# nandboard.net
KiCad netlist of a schematic drawn in EAGLE
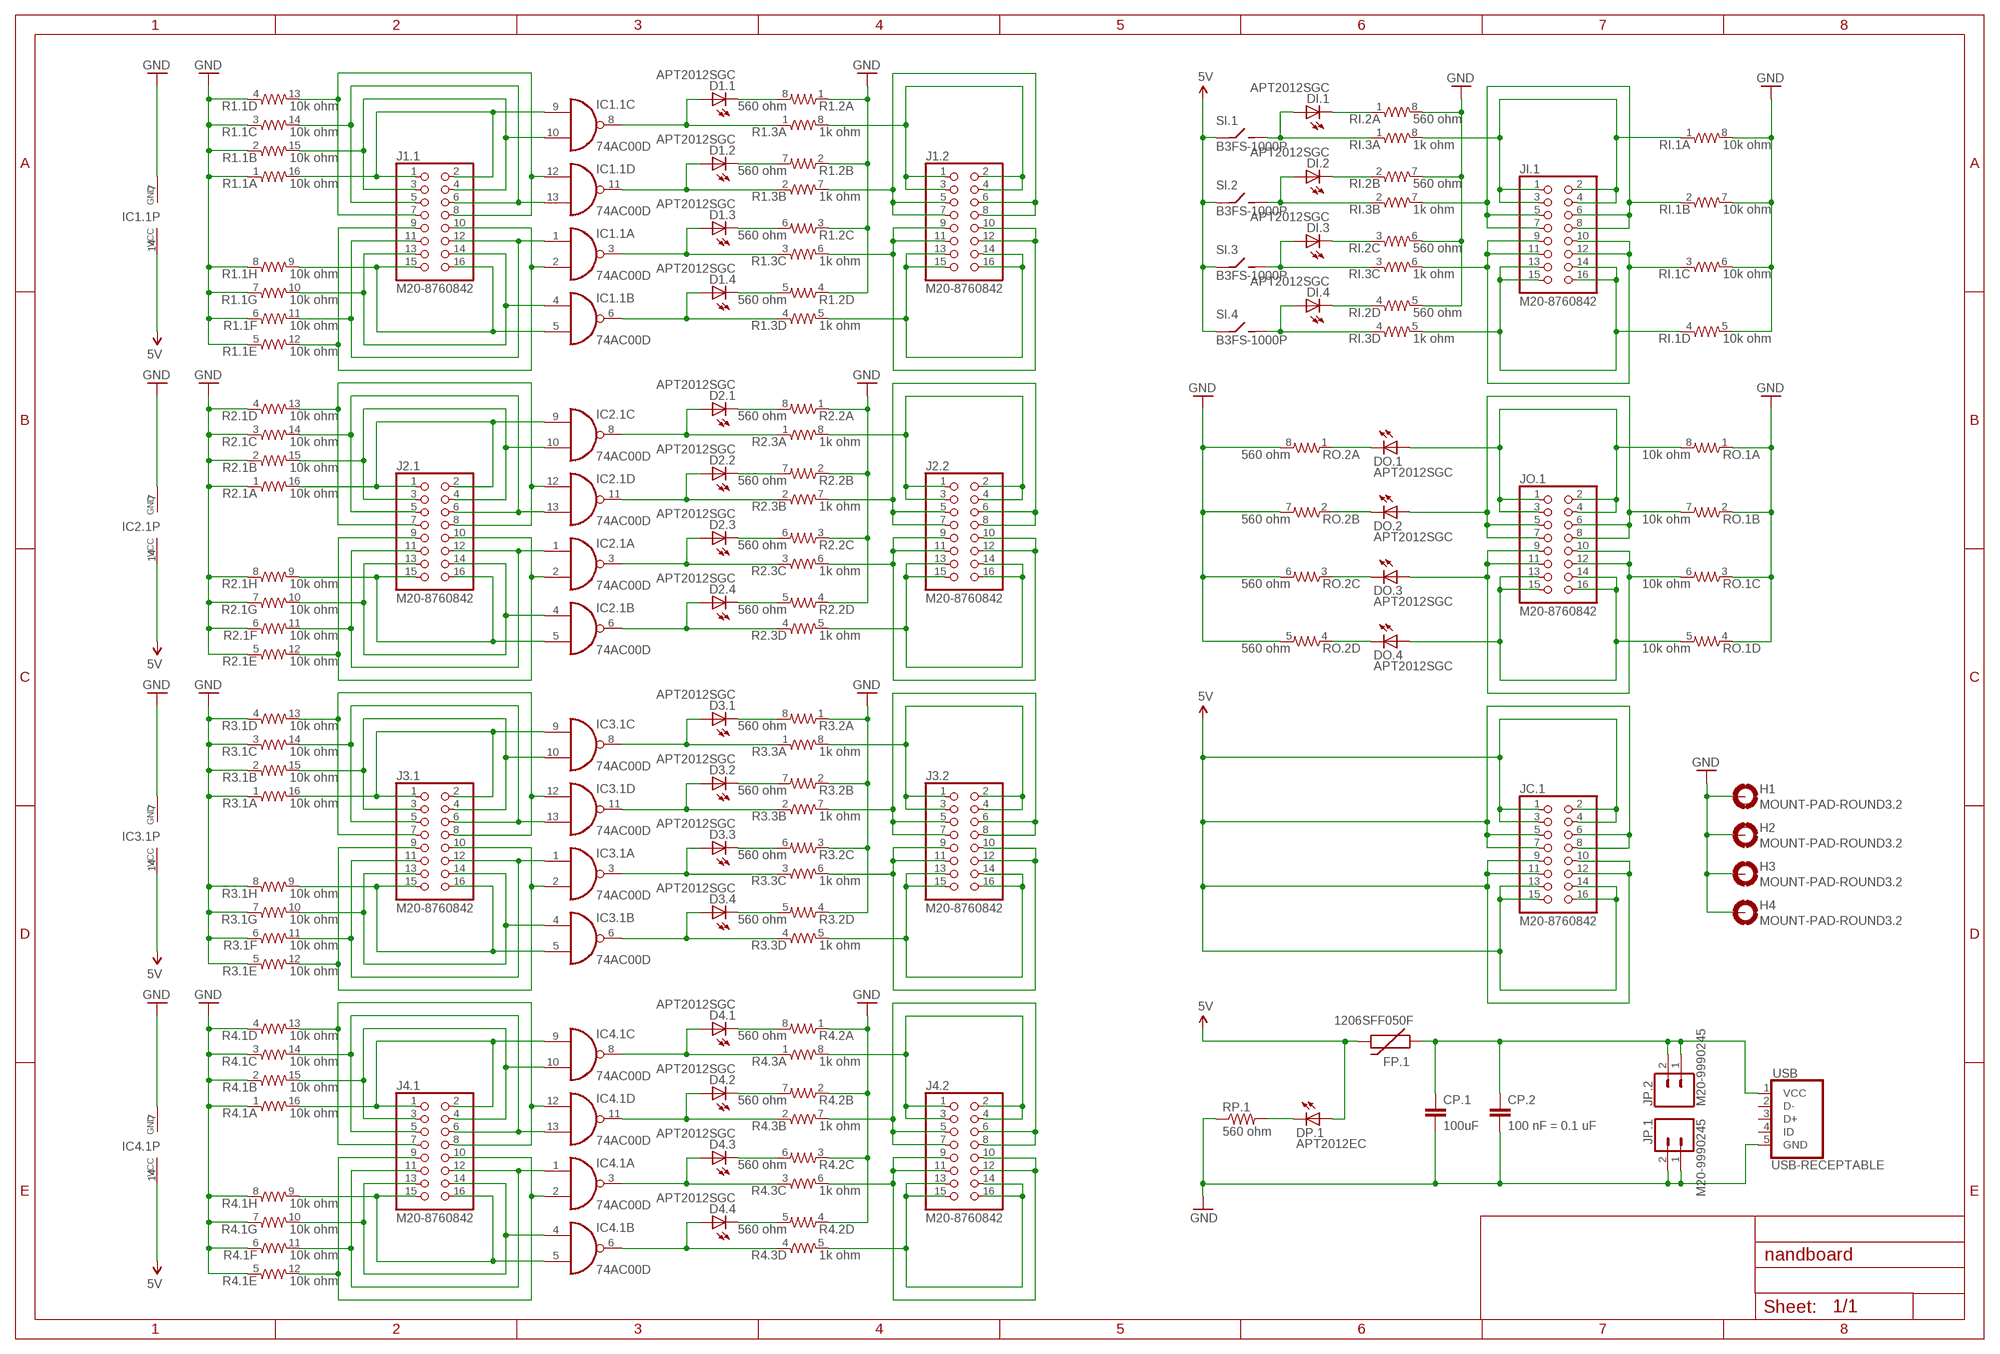
[diagram p0: schematic, sheet 1]

(export (version "E")
  (design (tool "Eeschema 10.0.6"))
  (components
    (comp (ref "CP.1")
      (value "100uF")
      (footprint "eagle-import:C1210")
      (libsource (lib "eagle-import") (part "C-EUC1210"))
    )
    (comp (ref "CP.2")
      (value "100 nF = 0.1 uF")
      (footprint "eagle-import:C0805")
      (libsource (lib "eagle-import") (part "C-EUC0805"))
    )
    (comp (ref "D1.1")
      (value "APT2012SGC")
      (footprint "eagle-import:CHIPLED_0805")
      (libsource (lib "eagle-import") (part "LEDCHIPLED_0805"))
    )
    (comp (ref "D1.2")
      (value "APT2012SGC")
      (footprint "eagle-import:CHIPLED_0805")
      (libsource (lib "eagle-import") (part "LEDCHIPLED_0805"))
    )
    (comp (ref "D1.3")
      (value "APT2012SGC")
      (footprint "eagle-import:CHIPLED_0805")
      (libsource (lib "eagle-import") (part "LEDCHIPLED_0805"))
    )
    (comp (ref "D1.4")
      (value "APT2012SGC")
      (footprint "eagle-import:CHIPLED_0805")
      (libsource (lib "eagle-import") (part "LEDCHIPLED_0805"))
    )
    (comp (ref "D2.1")
      (value "APT2012SGC")
      (footprint "eagle-import:CHIPLED_0805")
      (libsource (lib "eagle-import") (part "LEDCHIPLED_0805"))
    )
    (comp (ref "D2.2")
      (value "APT2012SGC")
      (footprint "eagle-import:CHIPLED_0805")
      (libsource (lib "eagle-import") (part "LEDCHIPLED_0805"))
    )
    (comp (ref "D2.3")
      (value "APT2012SGC")
      (footprint "eagle-import:CHIPLED_0805")
      (libsource (lib "eagle-import") (part "LEDCHIPLED_0805"))
    )
    (comp (ref "D2.4")
      (value "APT2012SGC")
      (footprint "eagle-import:CHIPLED_0805")
      (libsource (lib "eagle-import") (part "LEDCHIPLED_0805"))
    )
    (comp (ref "D3.1")
      (value "APT2012SGC")
      (footprint "eagle-import:CHIPLED_0805")
      (libsource (lib "eagle-import") (part "LEDCHIPLED_0805"))
    )
    (comp (ref "D3.2")
      (value "APT2012SGC")
      (footprint "eagle-import:CHIPLED_0805")
      (libsource (lib "eagle-import") (part "LEDCHIPLED_0805"))
    )
    (comp (ref "D3.3")
      (value "APT2012SGC")
      (footprint "eagle-import:CHIPLED_0805")
      (libsource (lib "eagle-import") (part "LEDCHIPLED_0805"))
    )
    (comp (ref "D3.4")
      (value "APT2012SGC")
      (footprint "eagle-import:CHIPLED_0805")
      (libsource (lib "eagle-import") (part "LEDCHIPLED_0805"))
    )
    (comp (ref "D4.1")
      (value "APT2012SGC")
      (footprint "eagle-import:CHIPLED_0805")
      (libsource (lib "eagle-import") (part "LEDCHIPLED_0805"))
    )
    (comp (ref "D4.2")
      (value "APT2012SGC")
      (footprint "eagle-import:CHIPLED_0805")
      (libsource (lib "eagle-import") (part "LEDCHIPLED_0805"))
    )
    (comp (ref "D4.3")
      (value "APT2012SGC")
      (footprint "eagle-import:CHIPLED_0805")
      (libsource (lib "eagle-import") (part "LEDCHIPLED_0805"))
    )
    (comp (ref "D4.4")
      (value "APT2012SGC")
      (footprint "eagle-import:CHIPLED_0805")
      (libsource (lib "eagle-import") (part "LEDCHIPLED_0805"))
    )
    (comp (ref "DI.1")
      (value "APT2012SGC")
      (footprint "eagle-import:CHIPLED_0805")
      (libsource (lib "eagle-import") (part "LEDCHIPLED_0805"))
    )
    (comp (ref "DI.2")
      (value "APT2012SGC")
      (footprint "eagle-import:CHIPLED_0805")
      (libsource (lib "eagle-import") (part "LEDCHIPLED_0805"))
    )
    (comp (ref "DI.3")
      (value "APT2012SGC")
      (footprint "eagle-import:CHIPLED_0805")
      (libsource (lib "eagle-import") (part "LEDCHIPLED_0805"))
    )
    (comp (ref "DI.4")
      (value "APT2012SGC")
      (footprint "eagle-import:CHIPLED_0805")
      (libsource (lib "eagle-import") (part "LEDCHIPLED_0805"))
    )
    (comp (ref "DO.1")
      (value "APT2012SGC")
      (footprint "eagle-import:CHIPLED_0805")
      (libsource (lib "eagle-import") (part "LEDCHIPLED_0805"))
    )
    (comp (ref "DO.2")
      (value "APT2012SGC")
      (footprint "eagle-import:CHIPLED_0805")
      (libsource (lib "eagle-import") (part "LEDCHIPLED_0805"))
    )
    (comp (ref "DO.3")
      (value "APT2012SGC")
      (footprint "eagle-import:CHIPLED_0805")
      (libsource (lib "eagle-import") (part "LEDCHIPLED_0805"))
    )
    (comp (ref "DO.4")
      (value "APT2012SGC")
      (footprint "eagle-import:CHIPLED_0805")
      (libsource (lib "eagle-import") (part "LEDCHIPLED_0805"))
    )
    (comp (ref "DP.1")
      (value "APT2012EC")
      (footprint "eagle-import:CHIPLED_0805")
      (libsource (lib "eagle-import") (part "LEDCHIPLED_0805"))
    )
    (comp (ref "FP.1")
      (value "1206SFF050F")
      (footprint "eagle-import:PTC-1206")
      (libsource (lib "eagle-import") (part "PTCSMD"))
    )
    (comp (ref "H1")
      (value "MOUNT-PAD-ROUND3.2")
      (footprint "eagle-import:3,2-PAD")
      (libsource (lib "eagle-import") (part "MOUNT-PAD-ROUND3.2"))
    )
    (comp (ref "H2")
      (value "MOUNT-PAD-ROUND3.2")
      (footprint "eagle-import:3,2-PAD")
      (libsource (lib "eagle-import") (part "MOUNT-PAD-ROUND3.2"))
    )
    (comp (ref "H3")
      (value "MOUNT-PAD-ROUND3.2")
      (footprint "eagle-import:3,2-PAD")
      (libsource (lib "eagle-import") (part "MOUNT-PAD-ROUND3.2"))
    )
    (comp (ref "H4")
      (value "MOUNT-PAD-ROUND3.2")
      (footprint "eagle-import:3,2-PAD")
      (libsource (lib "eagle-import") (part "MOUNT-PAD-ROUND3.2"))
    )
    (comp (ref "IC1.1")
      (value "74AC00D")
      (footprint "eagle-import:SO14")
      (libsource (lib "eagle-import") (part "7400DAC"))
    )
    (comp (ref "IC2.1")
      (value "74AC00D")
      (footprint "eagle-import:SO14")
      (libsource (lib "eagle-import") (part "7400DAC"))
    )
    (comp (ref "IC3.1")
      (value "74AC00D")
      (footprint "eagle-import:SO14")
      (libsource (lib "eagle-import") (part "7400DAC"))
    )
    (comp (ref "IC4.1")
      (value "74AC00D")
      (footprint "eagle-import:SO14")
      (libsource (lib "eagle-import") (part "7400DAC"))
    )
    (comp (ref "J1.1")
      (value "M20-8760842")
      (footprint "eagle-import:2X08_SMT")
      (libsource (lib "eagle-import") (part "PINHD-2X8SMT"))
    )
    (comp (ref "J1.2")
      (value "M20-8760842")
      (footprint "eagle-import:2X08_SMT")
      (libsource (lib "eagle-import") (part "PINHD-2X8SMT"))
    )
    (comp (ref "J2.1")
      (value "M20-8760842")
      (footprint "eagle-import:2X08_SMT")
      (libsource (lib "eagle-import") (part "PINHD-2X8SMT"))
    )
    (comp (ref "J2.2")
      (value "M20-8760842")
      (footprint "eagle-import:2X08_SMT")
      (libsource (lib "eagle-import") (part "PINHD-2X8SMT"))
    )
    (comp (ref "J3.1")
      (value "M20-8760842")
      (footprint "eagle-import:2X08_SMT")
      (libsource (lib "eagle-import") (part "PINHD-2X8SMT"))
    )
    (comp (ref "J3.2")
      (value "M20-8760842")
      (footprint "eagle-import:2X08_SMT")
      (libsource (lib "eagle-import") (part "PINHD-2X8SMT"))
    )
    (comp (ref "J4.1")
      (value "M20-8760842")
      (footprint "eagle-import:2X08_SMT")
      (libsource (lib "eagle-import") (part "PINHD-2X8SMT"))
    )
    (comp (ref "J4.2")
      (value "M20-8760842")
      (footprint "eagle-import:2X08_SMT")
      (libsource (lib "eagle-import") (part "PINHD-2X8SMT"))
    )
    (comp (ref "JC.1")
      (value "M20-8760842")
      (footprint "eagle-import:2X08_SMT")
      (libsource (lib "eagle-import") (part "PINHD-2X8SMT"))
    )
    (comp (ref "JI.1")
      (value "M20-8760842")
      (footprint "eagle-import:2X08_SMT")
      (libsource (lib "eagle-import") (part "PINHD-2X8SMT"))
    )
    (comp (ref "JO.1")
      (value "M20-8760842")
      (footprint "eagle-import:2X08_SMT")
      (libsource (lib "eagle-import") (part "PINHD-2X8SMT"))
    )
    (comp (ref "JP.1")
      (value "M20-9990245")
      (footprint "eagle-import:1X02")
      (libsource (lib "eagle-import") (part "CONN_02"))
    )
    (comp (ref "JP.2")
      (value "M20-9990245")
      (footprint "eagle-import:1X02")
      (libsource (lib "eagle-import") (part "CONN_02"))
    )
    (comp (ref "R1.1")
      (value "10k ohm")
      (footprint "eagle-import:742-16")
      (libsource (lib "eagle-import") (part "742-16_S"))
    )
    (comp (ref "R1.2")
      (value "560 ohm")
      (footprint "eagle-import:742-8")
      (libsource (lib "eagle-import") (part "742-8_S"))
    )
    (comp (ref "R1.3")
      (value "1k ohm")
      (footprint "eagle-import:742-8")
      (libsource (lib "eagle-import") (part "742-8_S"))
    )
    (comp (ref "R2.1")
      (value "10k ohm")
      (footprint "eagle-import:742-16")
      (libsource (lib "eagle-import") (part "742-16_S"))
    )
    (comp (ref "R2.2")
      (value "560 ohm")
      (footprint "eagle-import:742-8")
      (libsource (lib "eagle-import") (part "742-8_S"))
    )
    (comp (ref "R2.3")
      (value "1k ohm")
      (footprint "eagle-import:742-8")
      (libsource (lib "eagle-import") (part "742-8_S"))
    )
    (comp (ref "R3.1")
      (value "10k ohm")
      (footprint "eagle-import:742-16")
      (libsource (lib "eagle-import") (part "742-16_S"))
    )
    (comp (ref "R3.2")
      (value "560 ohm")
      (footprint "eagle-import:742-8")
      (libsource (lib "eagle-import") (part "742-8_S"))
    )
    (comp (ref "R3.3")
      (value "1k ohm")
      (footprint "eagle-import:742-8")
      (libsource (lib "eagle-import") (part "742-8_S"))
    )
    (comp (ref "R4.1")
      (value "10k ohm")
      (footprint "eagle-import:742-16")
      (libsource (lib "eagle-import") (part "742-16_S"))
    )
    (comp (ref "R4.2")
      (value "560 ohm")
      (footprint "eagle-import:742-8")
      (libsource (lib "eagle-import") (part "742-8_S"))
    )
    (comp (ref "R4.3")
      (value "1k ohm")
      (footprint "eagle-import:742-8")
      (libsource (lib "eagle-import") (part "742-8_S"))
    )
    (comp (ref "RI.1")
      (value "10k ohm")
      (footprint "eagle-import:742-8")
      (libsource (lib "eagle-import") (part "742-8_S"))
    )
    (comp (ref "RI.2")
      (value "560 ohm")
      (footprint "eagle-import:742-8")
      (libsource (lib "eagle-import") (part "742-8_S"))
    )
    (comp (ref "RI.3")
      (value "1k ohm")
      (footprint "eagle-import:742-8")
      (libsource (lib "eagle-import") (part "742-8_S"))
    )
    (comp (ref "RO.1")
      (value "10k ohm")
      (footprint "eagle-import:742-8")
      (libsource (lib "eagle-import") (part "742-8_S"))
    )
    (comp (ref "RO.2")
      (value "560 ohm")
      (footprint "eagle-import:742-8")
      (libsource (lib "eagle-import") (part "742-8_S"))
    )
    (comp (ref "RP.1")
      (value "560 ohm")
      (footprint "eagle-import:R0603")
      (libsource (lib "eagle-import") (part "R-US_R0603"))
    )
    (comp (ref "SI.1")
      (value "B3FS-1000P")
      (footprint "eagle-import:B3FS-1000")
      (libsource (lib "eagle-import") (part "SPSTB3FS-1000"))
    )
    (comp (ref "SI.2")
      (value "B3FS-1000P")
      (footprint "eagle-import:B3FS-1000")
      (libsource (lib "eagle-import") (part "SPSTB3FS-1000"))
    )
    (comp (ref "SI.3")
      (value "B3FS-1000P")
      (footprint "eagle-import:B3FS-1000")
      (libsource (lib "eagle-import") (part "SPSTB3FS-1000"))
    )
    (comp (ref "SI.4")
      (value "B3FS-1000P")
      (footprint "eagle-import:B3FS-1000")
      (libsource (lib "eagle-import") (part "SPSTB3FS-1000"))
    )
    (comp (ref "USB")
      (value "USB-RECEPTABLE")
      (footprint "eagle-import:FCI-10103594-0001LF")
      (libsource (lib "eagle-import") (part "USB-RECEPTABLE"))
    )
  )
  (nets
    (net (code "1") (name "5V") (class "Default")
      (node (ref "DP.1") (pin "A") (pinfunction "A_A") (pintype "passive"))
      (node (ref "FP.1") (pin "2") (pinfunction "2_2") (pintype "bidirectional"))
      (node (ref "IC1.1") (pin "14") (pinfunction "VCC_14") (pintype "power_in"))
      (node (ref "IC2.1") (pin "14") (pinfunction "VCC_14") (pintype "power_in"))
      (node (ref "IC3.1") (pin "14") (pinfunction "VCC_14") (pintype "power_in"))
      (node (ref "IC4.1") (pin "14") (pinfunction "VCC_14") (pintype "power_in"))
      (node (ref "JC.1") (pin "1") (pinfunction "1_1") (pintype "passive"))
      (node (ref "JC.1") (pin "10") (pinfunction "10_10") (pintype "passive"))
      (node (ref "JC.1") (pin "11") (pinfunction "11_11") (pintype "passive"))
      (node (ref "JC.1") (pin "12") (pinfunction "12_12") (pintype "passive"))
      (node (ref "JC.1") (pin "13") (pinfunction "13_13") (pintype "passive"))
      (node (ref "JC.1") (pin "14") (pinfunction "14_14") (pintype "passive"))
      (node (ref "JC.1") (pin "15") (pinfunction "15_15") (pintype "passive"))
      (node (ref "JC.1") (pin "16") (pinfunction "16_16") (pintype "passive"))
      (node (ref "JC.1") (pin "2") (pinfunction "2_2") (pintype "passive"))
      (node (ref "JC.1") (pin "3") (pinfunction "3_3") (pintype "passive"))
      (node (ref "JC.1") (pin "4") (pinfunction "4_4") (pintype "passive"))
      (node (ref "JC.1") (pin "5") (pinfunction "5_5") (pintype "passive"))
      (node (ref "JC.1") (pin "6") (pinfunction "6_6") (pintype "passive"))
      (node (ref "JC.1") (pin "7") (pinfunction "7_7") (pintype "passive"))
      (node (ref "JC.1") (pin "8") (pinfunction "8_8") (pintype "passive"))
      (node (ref "JC.1") (pin "9") (pinfunction "9_9") (pintype "passive"))
      (node (ref "SI.1") (pin "1") (pinfunction "A_1") (pintype "bidirectional"))
      (node (ref "SI.1") (pin "2") (pinfunction "A_2") (pintype "bidirectional"))
      (node (ref "SI.2") (pin "1") (pinfunction "A_1") (pintype "bidirectional"))
      (node (ref "SI.2") (pin "2") (pinfunction "A_2") (pintype "bidirectional"))
      (node (ref "SI.3") (pin "1") (pinfunction "A_1") (pintype "bidirectional"))
      (node (ref "SI.3") (pin "2") (pinfunction "A_2") (pintype "bidirectional"))
      (node (ref "SI.4") (pin "1") (pinfunction "A_1") (pintype "bidirectional"))
      (node (ref "SI.4") (pin "2") (pinfunction "A_2") (pintype "bidirectional"))
    )
    (net (code "2") (name "GND") (class "Default")
      (node (ref "CP.1") (pin "2") (pinfunction "2_2") (pintype "passive"))
      (node (ref "CP.2") (pin "2") (pinfunction "2_2") (pintype "passive"))
      (node (ref "H1") (pin "B3,2") (pinfunction "MOUNT_B3,2") (pintype "passive"))
      (node (ref "H2") (pin "B3,2") (pinfunction "MOUNT_B3,2") (pintype "passive"))
      (node (ref "H3") (pin "B3,2") (pinfunction "MOUNT_B3,2") (pintype "passive"))
      (node (ref "H4") (pin "B3,2") (pinfunction "MOUNT_B3,2") (pintype "passive"))
      (node (ref "IC1.1") (pin "7") (pinfunction "GND_7") (pintype "power_in"))
      (node (ref "IC2.1") (pin "7") (pinfunction "GND_7") (pintype "power_in"))
      (node (ref "IC3.1") (pin "7") (pinfunction "GND_7") (pintype "power_in"))
      (node (ref "IC4.1") (pin "7") (pinfunction "GND_7") (pintype "power_in"))
      (node (ref "JP.1") (pin "1") (pinfunction "1_1") (pintype "passive"))
      (node (ref "JP.1") (pin "2") (pinfunction "2_2") (pintype "passive"))
      (node (ref "R1.1") (pin "1") (pinfunction "1_1") (pintype "passive"))
      (node (ref "R1.1") (pin "2") (pinfunction "1_2") (pintype "passive"))
      (node (ref "R1.1") (pin "3") (pinfunction "1_3") (pintype "passive"))
      (node (ref "R1.1") (pin "4") (pinfunction "1_4") (pintype "passive"))
      (node (ref "R1.1") (pin "5") (pinfunction "1_5") (pintype "passive"))
      (node (ref "R1.1") (pin "6") (pinfunction "1_6") (pintype "passive"))
      (node (ref "R1.1") (pin "7") (pinfunction "1_7") (pintype "passive"))
      (node (ref "R1.1") (pin "8") (pinfunction "1_8") (pintype "passive"))
      (node (ref "R1.2") (pin "1") (pinfunction "1_1") (pintype "passive"))
      (node (ref "R1.2") (pin "2") (pinfunction "1_2") (pintype "passive"))
      (node (ref "R1.2") (pin "3") (pinfunction "1_3") (pintype "passive"))
      (node (ref "R1.2") (pin "4") (pinfunction "1_4") (pintype "passive"))
      (node (ref "R2.1") (pin "1") (pinfunction "1_1") (pintype "passive"))
      (node (ref "R2.1") (pin "2") (pinfunction "1_2") (pintype "passive"))
      (node (ref "R2.1") (pin "3") (pinfunction "1_3") (pintype "passive"))
      (node (ref "R2.1") (pin "4") (pinfunction "1_4") (pintype "passive"))
      (node (ref "R2.1") (pin "5") (pinfunction "1_5") (pintype "passive"))
      (node (ref "R2.1") (pin "6") (pinfunction "1_6") (pintype "passive"))
      (node (ref "R2.1") (pin "7") (pinfunction "1_7") (pintype "passive"))
      (node (ref "R2.1") (pin "8") (pinfunction "1_8") (pintype "passive"))
      (node (ref "R2.2") (pin "1") (pinfunction "1_1") (pintype "passive"))
      (node (ref "R2.2") (pin "2") (pinfunction "1_2") (pintype "passive"))
      (node (ref "R2.2") (pin "3") (pinfunction "1_3") (pintype "passive"))
      (node (ref "R2.2") (pin "4") (pinfunction "1_4") (pintype "passive"))
      (node (ref "R3.1") (pin "1") (pinfunction "1_1") (pintype "passive"))
      (node (ref "R3.1") (pin "2") (pinfunction "1_2") (pintype "passive"))
      (node (ref "R3.1") (pin "3") (pinfunction "1_3") (pintype "passive"))
      (node (ref "R3.1") (pin "4") (pinfunction "1_4") (pintype "passive"))
      (node (ref "R3.1") (pin "5") (pinfunction "1_5") (pintype "passive"))
      (node (ref "R3.1") (pin "6") (pinfunction "1_6") (pintype "passive"))
      (node (ref "R3.1") (pin "7") (pinfunction "1_7") (pintype "passive"))
      (node (ref "R3.1") (pin "8") (pinfunction "1_8") (pintype "passive"))
      (node (ref "R3.2") (pin "1") (pinfunction "1_1") (pintype "passive"))
      (node (ref "R3.2") (pin "2") (pinfunction "1_2") (pintype "passive"))
      (node (ref "R3.2") (pin "3") (pinfunction "1_3") (pintype "passive"))
      (node (ref "R3.2") (pin "4") (pinfunction "1_4") (pintype "passive"))
      (node (ref "R4.1") (pin "1") (pinfunction "1_1") (pintype "passive"))
      (node (ref "R4.1") (pin "2") (pinfunction "1_2") (pintype "passive"))
      (node (ref "R4.1") (pin "3") (pinfunction "1_3") (pintype "passive"))
      (node (ref "R4.1") (pin "4") (pinfunction "1_4") (pintype "passive"))
      (node (ref "R4.1") (pin "5") (pinfunction "1_5") (pintype "passive"))
      (node (ref "R4.1") (pin "6") (pinfunction "1_6") (pintype "passive"))
      (node (ref "R4.1") (pin "7") (pinfunction "1_7") (pintype "passive"))
      (node (ref "R4.1") (pin "8") (pinfunction "1_8") (pintype "passive"))
      (node (ref "R4.2") (pin "1") (pinfunction "1_1") (pintype "passive"))
      (node (ref "R4.2") (pin "2") (pinfunction "1_2") (pintype "passive"))
      (node (ref "R4.2") (pin "3") (pinfunction "1_3") (pintype "passive"))
      (node (ref "R4.2") (pin "4") (pinfunction "1_4") (pintype "passive"))
      (node (ref "RI.1") (pin "5") (pinfunction "2_5") (pintype "passive"))
      (node (ref "RI.1") (pin "6") (pinfunction "2_6") (pintype "passive"))
      (node (ref "RI.1") (pin "7") (pinfunction "2_7") (pintype "passive"))
      (node (ref "RI.1") (pin "8") (pinfunction "2_8") (pintype "passive"))
      (node (ref "RI.2") (pin "5") (pinfunction "2_5") (pintype "passive"))
      (node (ref "RI.2") (pin "6") (pinfunction "2_6") (pintype "passive"))
      (node (ref "RI.2") (pin "7") (pinfunction "2_7") (pintype "passive"))
      (node (ref "RI.2") (pin "8") (pinfunction "2_8") (pintype "passive"))
      (node (ref "RO.1") (pin "1") (pinfunction "1_1") (pintype "passive"))
      (node (ref "RO.1") (pin "2") (pinfunction "1_2") (pintype "passive"))
      (node (ref "RO.1") (pin "3") (pinfunction "1_3") (pintype "passive"))
      (node (ref "RO.1") (pin "4") (pinfunction "1_4") (pintype "passive"))
      (node (ref "RO.2") (pin "5") (pinfunction "2_5") (pintype "passive"))
      (node (ref "RO.2") (pin "6") (pinfunction "2_6") (pintype "passive"))
      (node (ref "RO.2") (pin "7") (pinfunction "2_7") (pintype "passive"))
      (node (ref "RO.2") (pin "8") (pinfunction "2_8") (pintype "passive"))
      (node (ref "RP.1") (pin "1") (pinfunction "1_1") (pintype "passive"))
      (node (ref "USB") (pin "5") (pinfunction "GND_5") (pintype "bidirectional"))
    )
    (net (code "3") (name "Net-(DI.1-PadA)") (class "Default")
      (node (ref "DI.1") (pin "A") (pinfunction "A_A") (pintype "passive"))
      (node (ref "RI.3") (pin "1") (pinfunction "1_1") (pintype "passive"))
      (node (ref "SI.1") (pin "3") (pinfunction "B_3") (pintype "bidirectional"))
      (node (ref "SI.1") (pin "4") (pinfunction "B_4") (pintype "bidirectional"))
    )
    (net (code "4") (name "Net-(DI.1-PadC)") (class "Default")
      (node (ref "DI.1") (pin "C") (pinfunction "C_C") (pintype "passive"))
      (node (ref "RI.2") (pin "1") (pinfunction "1_1") (pintype "passive"))
    )
    (net (code "5") (name "Net-(DO.1-PadC)") (class "Default")
      (node (ref "DO.1") (pin "C") (pinfunction "C_C") (pintype "passive"))
      (node (ref "RO.2") (pin "1") (pinfunction "1_1") (pintype "passive"))
    )
    (net (code "6") (name "Net-(DP.1-PadC)") (class "Default")
      (node (ref "DP.1") (pin "C") (pinfunction "C_C") (pintype "passive"))
      (node (ref "RP.1") (pin "2") (pinfunction "2_2") (pintype "passive"))
    )
    (net (code "7") (name "Net-(IC1.1A-I0)") (class "Default")
      (node (ref "IC1.1") (pin "1") (pinfunction "I0_1") (pintype "input"))
      (node (ref "J1.1") (pin "11") (pinfunction "11_11") (pintype "passive"))
      (node (ref "J1.1") (pin "12") (pinfunction "12_12") (pintype "passive"))
      (node (ref "R1.1") (pin "11") (pinfunction "2_11") (pintype "passive"))
    )
    (net (code "8") (name "Net-(IC1.1A-I1)") (class "Default")
      (node (ref "IC1.1") (pin "2") (pinfunction "I1_2") (pintype "input"))
      (node (ref "J1.1") (pin "10") (pinfunction "10_10") (pintype "passive"))
      (node (ref "J1.1") (pin "9") (pinfunction "9_9") (pintype "passive"))
      (node (ref "R1.1") (pin "12") (pinfunction "2_12") (pintype "passive"))
    )
    (net (code "9") (name "Net-(IC1.1A-O)") (class "Default")
      (node (ref "D1.3") (pin "A") (pinfunction "A_A") (pintype "passive"))
      (node (ref "IC1.1") (pin "3") (pinfunction "O_3") (pintype "output"))
      (node (ref "R1.3") (pin "3") (pinfunction "1_3") (pintype "passive"))
    )
    (net (code "10") (name "Net-(IC1.1B-I0)") (class "Default")
      (node (ref "IC1.1") (pin "4") (pinfunction "I0_4") (pintype "input"))
      (node (ref "J1.1") (pin "13") (pinfunction "13_13") (pintype "passive"))
      (node (ref "J1.1") (pin "14") (pinfunction "14_14") (pintype "passive"))
      (node (ref "R1.1") (pin "10") (pinfunction "2_10") (pintype "passive"))
    )
    (net (code "11") (name "Net-(IC1.1B-I1)") (class "Default")
      (node (ref "IC1.1") (pin "5") (pinfunction "I1_5") (pintype "input"))
      (node (ref "J1.1") (pin "15") (pinfunction "15_15") (pintype "passive"))
      (node (ref "J1.1") (pin "16") (pinfunction "16_16") (pintype "passive"))
      (node (ref "R1.1") (pin "9") (pinfunction "2_9") (pintype "passive"))
    )
    (net (code "12") (name "Net-(IC1.1B-O)") (class "Default")
      (node (ref "D1.4") (pin "A") (pinfunction "A_A") (pintype "passive"))
      (node (ref "IC1.1") (pin "6") (pinfunction "O_6") (pintype "output"))
      (node (ref "R1.3") (pin "4") (pinfunction "1_4") (pintype "passive"))
    )
    (net (code "13") (name "Net-(IC1.1C-I0)") (class "Default")
      (node (ref "IC1.1") (pin "9") (pinfunction "I0_9") (pintype "input"))
      (node (ref "J1.1") (pin "1") (pinfunction "1_1") (pintype "passive"))
      (node (ref "J1.1") (pin "2") (pinfunction "2_2") (pintype "passive"))
      (node (ref "R1.1") (pin "16") (pinfunction "2_16") (pintype "passive"))
    )
    (net (code "14") (name "Net-(IC1.1C-I1)") (class "Default")
      (node (ref "IC1.1") (pin "10") (pinfunction "I1_10") (pintype "input"))
      (node (ref "J1.1") (pin "3") (pinfunction "3_3") (pintype "passive"))
      (node (ref "J1.1") (pin "4") (pinfunction "4_4") (pintype "passive"))
      (node (ref "R1.1") (pin "15") (pinfunction "2_15") (pintype "passive"))
    )
    (net (code "15") (name "Net-(IC1.1C-O)") (class "Default")
      (node (ref "D1.1") (pin "A") (pinfunction "A_A") (pintype "passive"))
      (node (ref "IC1.1") (pin "8") (pinfunction "O_8") (pintype "output"))
      (node (ref "R1.3") (pin "1") (pinfunction "1_1") (pintype "passive"))
    )
    (net (code "16") (name "Net-(IC1.1D-I0)") (class "Default")
      (node (ref "IC1.1") (pin "12") (pinfunction "I0_12") (pintype "input"))
      (node (ref "J1.1") (pin "7") (pinfunction "7_7") (pintype "passive"))
      (node (ref "J1.1") (pin "8") (pinfunction "8_8") (pintype "passive"))
      (node (ref "R1.1") (pin "13") (pinfunction "2_13") (pintype "passive"))
    )
    (net (code "17") (name "Net-(IC1.1D-I1)") (class "Default")
      (node (ref "IC1.1") (pin "13") (pinfunction "I1_13") (pintype "input"))
      (node (ref "J1.1") (pin "5") (pinfunction "5_5") (pintype "passive"))
      (node (ref "J1.1") (pin "6") (pinfunction "6_6") (pintype "passive"))
      (node (ref "R1.1") (pin "14") (pinfunction "2_14") (pintype "passive"))
    )
    (net (code "18") (name "Net-(IC1.1D-O)") (class "Default")
      (node (ref "D1.2") (pin "A") (pinfunction "A_A") (pintype "passive"))
      (node (ref "IC1.1") (pin "11") (pinfunction "O_11") (pintype "output"))
      (node (ref "R1.3") (pin "2") (pinfunction "1_2") (pintype "passive"))
    )
    (net (code "19") (name "Net-(IC2.1A-I0)") (class "Default")
      (node (ref "IC2.1") (pin "1") (pinfunction "I0_1") (pintype "input"))
      (node (ref "J2.1") (pin "11") (pinfunction "11_11") (pintype "passive"))
      (node (ref "J2.1") (pin "12") (pinfunction "12_12") (pintype "passive"))
      (node (ref "R2.1") (pin "11") (pinfunction "2_11") (pintype "passive"))
    )
    (net (code "20") (name "Net-(IC2.1A-I1)") (class "Default")
      (node (ref "IC2.1") (pin "2") (pinfunction "I1_2") (pintype "input"))
      (node (ref "J2.1") (pin "10") (pinfunction "10_10") (pintype "passive"))
      (node (ref "J2.1") (pin "9") (pinfunction "9_9") (pintype "passive"))
      (node (ref "R2.1") (pin "12") (pinfunction "2_12") (pintype "passive"))
    )
    (net (code "21") (name "Net-(IC2.1A-O)") (class "Default")
      (node (ref "D2.3") (pin "A") (pinfunction "A_A") (pintype "passive"))
      (node (ref "IC2.1") (pin "3") (pinfunction "O_3") (pintype "output"))
      (node (ref "R2.3") (pin "3") (pinfunction "1_3") (pintype "passive"))
    )
    (net (code "22") (name "Net-(IC2.1B-I0)") (class "Default")
      (node (ref "IC2.1") (pin "4") (pinfunction "I0_4") (pintype "input"))
      (node (ref "J2.1") (pin "13") (pinfunction "13_13") (pintype "passive"))
      (node (ref "J2.1") (pin "14") (pinfunction "14_14") (pintype "passive"))
      (node (ref "R2.1") (pin "10") (pinfunction "2_10") (pintype "passive"))
    )
    (net (code "23") (name "Net-(IC2.1B-I1)") (class "Default")
      (node (ref "IC2.1") (pin "5") (pinfunction "I1_5") (pintype "input"))
      (node (ref "J2.1") (pin "15") (pinfunction "15_15") (pintype "passive"))
      (node (ref "J2.1") (pin "16") (pinfunction "16_16") (pintype "passive"))
      (node (ref "R2.1") (pin "9") (pinfunction "2_9") (pintype "passive"))
    )
    (net (code "24") (name "Net-(IC2.1B-O)") (class "Default")
      (node (ref "D2.4") (pin "A") (pinfunction "A_A") (pintype "passive"))
      (node (ref "IC2.1") (pin "6") (pinfunction "O_6") (pintype "output"))
      (node (ref "R2.3") (pin "4") (pinfunction "1_4") (pintype "passive"))
    )
    (net (code "25") (name "Net-(IC2.1C-I0)") (class "Default")
      (node (ref "IC2.1") (pin "9") (pinfunction "I0_9") (pintype "input"))
      (node (ref "J2.1") (pin "1") (pinfunction "1_1") (pintype "passive"))
      (node (ref "J2.1") (pin "2") (pinfunction "2_2") (pintype "passive"))
      (node (ref "R2.1") (pin "16") (pinfunction "2_16") (pintype "passive"))
    )
    (net (code "26") (name "Net-(IC2.1C-I1)") (class "Default")
      (node (ref "IC2.1") (pin "10") (pinfunction "I1_10") (pintype "input"))
      (node (ref "J2.1") (pin "3") (pinfunction "3_3") (pintype "passive"))
      (node (ref "J2.1") (pin "4") (pinfunction "4_4") (pintype "passive"))
      (node (ref "R2.1") (pin "15") (pinfunction "2_15") (pintype "passive"))
    )
    (net (code "27") (name "Net-(IC2.1C-O)") (class "Default")
      (node (ref "D2.1") (pin "A") (pinfunction "A_A") (pintype "passive"))
      (node (ref "IC2.1") (pin "8") (pinfunction "O_8") (pintype "output"))
      (node (ref "R2.3") (pin "1") (pinfunction "1_1") (pintype "passive"))
    )
    (net (code "28") (name "Net-(IC2.1D-I0)") (class "Default")
      (node (ref "IC2.1") (pin "12") (pinfunction "I0_12") (pintype "input"))
      (node (ref "J2.1") (pin "7") (pinfunction "7_7") (pintype "passive"))
      (node (ref "J2.1") (pin "8") (pinfunction "8_8") (pintype "passive"))
      (node (ref "R2.1") (pin "13") (pinfunction "2_13") (pintype "passive"))
    )
    (net (code "29") (name "Net-(IC2.1D-I1)") (class "Default")
      (node (ref "IC2.1") (pin "13") (pinfunction "I1_13") (pintype "input"))
      (node (ref "J2.1") (pin "5") (pinfunction "5_5") (pintype "passive"))
      (node (ref "J2.1") (pin "6") (pinfunction "6_6") (pintype "passive"))
      (node (ref "R2.1") (pin "14") (pinfunction "2_14") (pintype "passive"))
    )
    (net (code "30") (name "Net-(IC2.1D-O)") (class "Default")
      (node (ref "D2.2") (pin "A") (pinfunction "A_A") (pintype "passive"))
      (node (ref "IC2.1") (pin "11") (pinfunction "O_11") (pintype "output"))
      (node (ref "R2.3") (pin "2") (pinfunction "1_2") (pintype "passive"))
    )
    (net (code "31") (name "Net-(IC3.1A-I0)") (class "Default")
      (node (ref "IC3.1") (pin "1") (pinfunction "I0_1") (pintype "input"))
      (node (ref "J3.1") (pin "11") (pinfunction "11_11") (pintype "passive"))
      (node (ref "J3.1") (pin "12") (pinfunction "12_12") (pintype "passive"))
      (node (ref "R3.1") (pin "11") (pinfunction "2_11") (pintype "passive"))
    )
    (net (code "32") (name "Net-(IC3.1A-I1)") (class "Default")
      (node (ref "IC3.1") (pin "2") (pinfunction "I1_2") (pintype "input"))
      (node (ref "J3.1") (pin "10") (pinfunction "10_10") (pintype "passive"))
      (node (ref "J3.1") (pin "9") (pinfunction "9_9") (pintype "passive"))
      (node (ref "R3.1") (pin "12") (pinfunction "2_12") (pintype "passive"))
    )
    (net (code "33") (name "Net-(IC3.1A-O)") (class "Default")
      (node (ref "D3.3") (pin "A") (pinfunction "A_A") (pintype "passive"))
      (node (ref "IC3.1") (pin "3") (pinfunction "O_3") (pintype "output"))
      (node (ref "R3.3") (pin "3") (pinfunction "1_3") (pintype "passive"))
    )
    (net (code "34") (name "Net-(IC3.1B-I0)") (class "Default")
      (node (ref "IC3.1") (pin "4") (pinfunction "I0_4") (pintype "input"))
      (node (ref "J3.1") (pin "13") (pinfunction "13_13") (pintype "passive"))
      (node (ref "J3.1") (pin "14") (pinfunction "14_14") (pintype "passive"))
      (node (ref "R3.1") (pin "10") (pinfunction "2_10") (pintype "passive"))
    )
    (net (code "35") (name "Net-(IC3.1B-I1)") (class "Default")
      (node (ref "IC3.1") (pin "5") (pinfunction "I1_5") (pintype "input"))
      (node (ref "J3.1") (pin "15") (pinfunction "15_15") (pintype "passive"))
      (node (ref "J3.1") (pin "16") (pinfunction "16_16") (pintype "passive"))
      (node (ref "R3.1") (pin "9") (pinfunction "2_9") (pintype "passive"))
    )
    (net (code "36") (name "Net-(IC3.1B-O)") (class "Default")
      (node (ref "D3.4") (pin "A") (pinfunction "A_A") (pintype "passive"))
      (node (ref "IC3.1") (pin "6") (pinfunction "O_6") (pintype "output"))
      (node (ref "R3.3") (pin "4") (pinfunction "1_4") (pintype "passive"))
    )
    (net (code "37") (name "Net-(IC3.1C-I0)") (class "Default")
      (node (ref "IC3.1") (pin "9") (pinfunction "I0_9") (pintype "input"))
      (node (ref "J3.1") (pin "1") (pinfunction "1_1") (pintype "passive"))
      (node (ref "J3.1") (pin "2") (pinfunction "2_2") (pintype "passive"))
      (node (ref "R3.1") (pin "16") (pinfunction "2_16") (pintype "passive"))
    )
    (net (code "38") (name "Net-(IC3.1C-I1)") (class "Default")
      (node (ref "IC3.1") (pin "10") (pinfunction "I1_10") (pintype "input"))
      (node (ref "J3.1") (pin "3") (pinfunction "3_3") (pintype "passive"))
      (node (ref "J3.1") (pin "4") (pinfunction "4_4") (pintype "passive"))
      (node (ref "R3.1") (pin "15") (pinfunction "2_15") (pintype "passive"))
    )
    (net (code "39") (name "Net-(IC3.1C-O)") (class "Default")
      (node (ref "D3.1") (pin "A") (pinfunction "A_A") (pintype "passive"))
      (node (ref "IC3.1") (pin "8") (pinfunction "O_8") (pintype "output"))
      (node (ref "R3.3") (pin "1") (pinfunction "1_1") (pintype "passive"))
    )
    (net (code "40") (name "Net-(IC3.1D-I0)") (class "Default")
      (node (ref "IC3.1") (pin "12") (pinfunction "I0_12") (pintype "input"))
      (node (ref "J3.1") (pin "7") (pinfunction "7_7") (pintype "passive"))
      (node (ref "J3.1") (pin "8") (pinfunction "8_8") (pintype "passive"))
      (node (ref "R3.1") (pin "13") (pinfunction "2_13") (pintype "passive"))
    )
    (net (code "41") (name "Net-(IC3.1D-I1)") (class "Default")
      (node (ref "IC3.1") (pin "13") (pinfunction "I1_13") (pintype "input"))
      (node (ref "J3.1") (pin "5") (pinfunction "5_5") (pintype "passive"))
      (node (ref "J3.1") (pin "6") (pinfunction "6_6") (pintype "passive"))
      (node (ref "R3.1") (pin "14") (pinfunction "2_14") (pintype "passive"))
    )
    (net (code "42") (name "Net-(IC3.1D-O)") (class "Default")
      (node (ref "D3.2") (pin "A") (pinfunction "A_A") (pintype "passive"))
      (node (ref "IC3.1") (pin "11") (pinfunction "O_11") (pintype "output"))
      (node (ref "R3.3") (pin "2") (pinfunction "1_2") (pintype "passive"))
    )
    (net (code "43") (name "Net-(IC4.1A-I0)") (class "Default")
      (node (ref "IC4.1") (pin "1") (pinfunction "I0_1") (pintype "input"))
      (node (ref "J4.1") (pin "11") (pinfunction "11_11") (pintype "passive"))
      (node (ref "J4.1") (pin "12") (pinfunction "12_12") (pintype "passive"))
      (node (ref "R4.1") (pin "11") (pinfunction "2_11") (pintype "passive"))
    )
    (net (code "44") (name "Net-(IC4.1A-I1)") (class "Default")
      (node (ref "IC4.1") (pin "2") (pinfunction "I1_2") (pintype "input"))
      (node (ref "J4.1") (pin "10") (pinfunction "10_10") (pintype "passive"))
      (node (ref "J4.1") (pin "9") (pinfunction "9_9") (pintype "passive"))
      (node (ref "R4.1") (pin "12") (pinfunction "2_12") (pintype "passive"))
    )
    (net (code "45") (name "Net-(IC4.1A-O)") (class "Default")
      (node (ref "D4.3") (pin "A") (pinfunction "A_A") (pintype "passive"))
      (node (ref "IC4.1") (pin "3") (pinfunction "O_3") (pintype "output"))
      (node (ref "R4.3") (pin "3") (pinfunction "1_3") (pintype "passive"))
    )
    (net (code "46") (name "Net-(IC4.1B-I0)") (class "Default")
      (node (ref "IC4.1") (pin "4") (pinfunction "I0_4") (pintype "input"))
      (node (ref "J4.1") (pin "13") (pinfunction "13_13") (pintype "passive"))
      (node (ref "J4.1") (pin "14") (pinfunction "14_14") (pintype "passive"))
      (node (ref "R4.1") (pin "10") (pinfunction "2_10") (pintype "passive"))
    )
    (net (code "47") (name "Net-(IC4.1B-I1)") (class "Default")
      (node (ref "IC4.1") (pin "5") (pinfunction "I1_5") (pintype "input"))
      (node (ref "J4.1") (pin "15") (pinfunction "15_15") (pintype "passive"))
      (node (ref "J4.1") (pin "16") (pinfunction "16_16") (pintype "passive"))
      (node (ref "R4.1") (pin "9") (pinfunction "2_9") (pintype "passive"))
    )
    (net (code "48") (name "Net-(IC4.1B-O)") (class "Default")
      (node (ref "D4.4") (pin "A") (pinfunction "A_A") (pintype "passive"))
      (node (ref "IC4.1") (pin "6") (pinfunction "O_6") (pintype "output"))
      (node (ref "R4.3") (pin "4") (pinfunction "1_4") (pintype "passive"))
    )
    (net (code "49") (name "Net-(IC4.1C-I0)") (class "Default")
      (node (ref "IC4.1") (pin "9") (pinfunction "I0_9") (pintype "input"))
      (node (ref "J4.1") (pin "1") (pinfunction "1_1") (pintype "passive"))
      (node (ref "J4.1") (pin "2") (pinfunction "2_2") (pintype "passive"))
      (node (ref "R4.1") (pin "16") (pinfunction "2_16") (pintype "passive"))
    )
    (net (code "50") (name "Net-(IC4.1C-I1)") (class "Default")
      (node (ref "IC4.1") (pin "10") (pinfunction "I1_10") (pintype "input"))
      (node (ref "J4.1") (pin "3") (pinfunction "3_3") (pintype "passive"))
      (node (ref "J4.1") (pin "4") (pinfunction "4_4") (pintype "passive"))
      (node (ref "R4.1") (pin "15") (pinfunction "2_15") (pintype "passive"))
    )
    (net (code "51") (name "Net-(IC4.1C-O)") (class "Default")
      (node (ref "D4.1") (pin "A") (pinfunction "A_A") (pintype "passive"))
      (node (ref "IC4.1") (pin "8") (pinfunction "O_8") (pintype "output"))
      (node (ref "R4.3") (pin "1") (pinfunction "1_1") (pintype "passive"))
    )
    (net (code "52") (name "Net-(IC4.1D-I0)") (class "Default")
      (node (ref "IC4.1") (pin "12") (pinfunction "I0_12") (pintype "input"))
      (node (ref "J4.1") (pin "7") (pinfunction "7_7") (pintype "passive"))
      (node (ref "J4.1") (pin "8") (pinfunction "8_8") (pintype "passive"))
      (node (ref "R4.1") (pin "13") (pinfunction "2_13") (pintype "passive"))
    )
    (net (code "53") (name "Net-(IC4.1D-I1)") (class "Default")
      (node (ref "IC4.1") (pin "13") (pinfunction "I1_13") (pintype "input"))
      (node (ref "J4.1") (pin "5") (pinfunction "5_5") (pintype "passive"))
      (node (ref "J4.1") (pin "6") (pinfunction "6_6") (pintype "passive"))
      (node (ref "R4.1") (pin "14") (pinfunction "2_14") (pintype "passive"))
    )
    (net (code "54") (name "Net-(IC4.1D-O)") (class "Default")
      (node (ref "D4.2") (pin "A") (pinfunction "A_A") (pintype "passive"))
      (node (ref "IC4.1") (pin "11") (pinfunction "O_11") (pintype "output"))
      (node (ref "R4.3") (pin "2") (pinfunction "1_2") (pintype "passive"))
    )
    (net (code "55") (name "Net-(R1.2A-2)") (class "Default")
      (node (ref "D1.1") (pin "C") (pinfunction "C_C") (pintype "passive"))
      (node (ref "R1.2") (pin "8") (pinfunction "2_8") (pintype "passive"))
    )
    (net (code "56") (name "Net-(R1.2B-2)") (class "Default")
      (node (ref "D1.2") (pin "C") (pinfunction "C_C") (pintype "passive"))
      (node (ref "R1.2") (pin "7") (pinfunction "2_7") (pintype "passive"))
    )
    (net (code "57") (name "Net-(R1.2C-2)") (class "Default")
      (node (ref "D1.3") (pin "C") (pinfunction "C_C") (pintype "passive"))
      (node (ref "R1.2") (pin "6") (pinfunction "2_6") (pintype "passive"))
    )
    (net (code "58") (name "Net-(R1.2D-2)") (class "Default")
      (node (ref "D1.4") (pin "C") (pinfunction "C_C") (pintype "passive"))
      (node (ref "R1.2") (pin "5") (pinfunction "2_5") (pintype "passive"))
    )
    (net (code "59") (name "Net-(R1.3A-2)") (class "Default")
      (node (ref "J1.2") (pin "1") (pinfunction "1_1") (pintype "passive"))
      (node (ref "J1.2") (pin "2") (pinfunction "2_2") (pintype "passive"))
      (node (ref "J1.2") (pin "3") (pinfunction "3_3") (pintype "passive"))
      (node (ref "J1.2") (pin "4") (pinfunction "4_4") (pintype "passive"))
      (node (ref "R1.3") (pin "8") (pinfunction "2_8") (pintype "passive"))
    )
    (net (code "60") (name "Net-(R1.3B-2)") (class "Default")
      (node (ref "J1.2") (pin "5") (pinfunction "5_5") (pintype "passive"))
      (node (ref "J1.2") (pin "6") (pinfunction "6_6") (pintype "passive"))
      (node (ref "J1.2") (pin "7") (pinfunction "7_7") (pintype "passive"))
      (node (ref "J1.2") (pin "8") (pinfunction "8_8") (pintype "passive"))
      (node (ref "R1.3") (pin "7") (pinfunction "2_7") (pintype "passive"))
    )
    (net (code "61") (name "Net-(R1.3C-2)") (class "Default")
      (node (ref "J1.2") (pin "10") (pinfunction "10_10") (pintype "passive"))
      (node (ref "J1.2") (pin "11") (pinfunction "11_11") (pintype "passive"))
      (node (ref "J1.2") (pin "12") (pinfunction "12_12") (pintype "passive"))
      (node (ref "J1.2") (pin "9") (pinfunction "9_9") (pintype "passive"))
      (node (ref "R1.3") (pin "6") (pinfunction "2_6") (pintype "passive"))
    )
    (net (code "62") (name "Net-(R1.3D-2)") (class "Default")
      (node (ref "J1.2") (pin "13") (pinfunction "13_13") (pintype "passive"))
      (node (ref "J1.2") (pin "14") (pinfunction "14_14") (pintype "passive"))
      (node (ref "J1.2") (pin "15") (pinfunction "15_15") (pintype "passive"))
      (node (ref "J1.2") (pin "16") (pinfunction "16_16") (pintype "passive"))
      (node (ref "R1.3") (pin "5") (pinfunction "2_5") (pintype "passive"))
    )
    (net (code "63") (name "Net-(R2.2A-2)") (class "Default")
      (node (ref "D2.1") (pin "C") (pinfunction "C_C") (pintype "passive"))
      (node (ref "R2.2") (pin "8") (pinfunction "2_8") (pintype "passive"))
    )
    (net (code "64") (name "Net-(R2.2B-2)") (class "Default")
      (node (ref "D2.2") (pin "C") (pinfunction "C_C") (pintype "passive"))
      (node (ref "R2.2") (pin "7") (pinfunction "2_7") (pintype "passive"))
    )
    (net (code "65") (name "Net-(R2.2C-2)") (class "Default")
      (node (ref "D2.3") (pin "C") (pinfunction "C_C") (pintype "passive"))
      (node (ref "R2.2") (pin "6") (pinfunction "2_6") (pintype "passive"))
    )
    (net (code "66") (name "Net-(R2.2D-2)") (class "Default")
      (node (ref "D2.4") (pin "C") (pinfunction "C_C") (pintype "passive"))
      (node (ref "R2.2") (pin "5") (pinfunction "2_5") (pintype "passive"))
    )
    (net (code "67") (name "Net-(R2.3A-2)") (class "Default")
      (node (ref "J2.2") (pin "1") (pinfunction "1_1") (pintype "passive"))
      (node (ref "J2.2") (pin "2") (pinfunction "2_2") (pintype "passive"))
      (node (ref "J2.2") (pin "3") (pinfunction "3_3") (pintype "passive"))
      (node (ref "J2.2") (pin "4") (pinfunction "4_4") (pintype "passive"))
      (node (ref "R2.3") (pin "8") (pinfunction "2_8") (pintype "passive"))
    )
    (net (code "68") (name "Net-(R2.3B-2)") (class "Default")
      (node (ref "J2.2") (pin "5") (pinfunction "5_5") (pintype "passive"))
      (node (ref "J2.2") (pin "6") (pinfunction "6_6") (pintype "passive"))
      (node (ref "J2.2") (pin "7") (pinfunction "7_7") (pintype "passive"))
      (node (ref "J2.2") (pin "8") (pinfunction "8_8") (pintype "passive"))
      (node (ref "R2.3") (pin "7") (pinfunction "2_7") (pintype "passive"))
    )
    (net (code "69") (name "Net-(R2.3C-2)") (class "Default")
      (node (ref "J2.2") (pin "10") (pinfunction "10_10") (pintype "passive"))
      (node (ref "J2.2") (pin "11") (pinfunction "11_11") (pintype "passive"))
      (node (ref "J2.2") (pin "12") (pinfunction "12_12") (pintype "passive"))
      (node (ref "J2.2") (pin "9") (pinfunction "9_9") (pintype "passive"))
      (node (ref "R2.3") (pin "6") (pinfunction "2_6") (pintype "passive"))
    )
    (net (code "70") (name "Net-(R2.3D-2)") (class "Default")
      (node (ref "J2.2") (pin "13") (pinfunction "13_13") (pintype "passive"))
      (node (ref "J2.2") (pin "14") (pinfunction "14_14") (pintype "passive"))
      (node (ref "J2.2") (pin "15") (pinfunction "15_15") (pintype "passive"))
      (node (ref "J2.2") (pin "16") (pinfunction "16_16") (pintype "passive"))
      (node (ref "R2.3") (pin "5") (pinfunction "2_5") (pintype "passive"))
    )
    (net (code "71") (name "Net-(R3.2A-2)") (class "Default")
      (node (ref "D3.1") (pin "C") (pinfunction "C_C") (pintype "passive"))
      (node (ref "R3.2") (pin "8") (pinfunction "2_8") (pintype "passive"))
    )
    (net (code "72") (name "Net-(R3.2B-2)") (class "Default")
      (node (ref "D3.2") (pin "C") (pinfunction "C_C") (pintype "passive"))
      (node (ref "R3.2") (pin "7") (pinfunction "2_7") (pintype "passive"))
    )
    (net (code "73") (name "Net-(R3.2C-2)") (class "Default")
      (node (ref "D3.3") (pin "C") (pinfunction "C_C") (pintype "passive"))
      (node (ref "R3.2") (pin "6") (pinfunction "2_6") (pintype "passive"))
    )
    (net (code "74") (name "Net-(R3.2D-2)") (class "Default")
      (node (ref "D3.4") (pin "C") (pinfunction "C_C") (pintype "passive"))
      (node (ref "R3.2") (pin "5") (pinfunction "2_5") (pintype "passive"))
    )
    (net (code "75") (name "Net-(R3.3A-2)") (class "Default")
      (node (ref "J3.2") (pin "1") (pinfunction "1_1") (pintype "passive"))
      (node (ref "J3.2") (pin "2") (pinfunction "2_2") (pintype "passive"))
      (node (ref "J3.2") (pin "3") (pinfunction "3_3") (pintype "passive"))
      (node (ref "J3.2") (pin "4") (pinfunction "4_4") (pintype "passive"))
      (node (ref "R3.3") (pin "8") (pinfunction "2_8") (pintype "passive"))
    )
    (net (code "76") (name "Net-(R3.3B-2)") (class "Default")
      (node (ref "J3.2") (pin "5") (pinfunction "5_5") (pintype "passive"))
      (node (ref "J3.2") (pin "6") (pinfunction "6_6") (pintype "passive"))
      (node (ref "J3.2") (pin "7") (pinfunction "7_7") (pintype "passive"))
      (node (ref "J3.2") (pin "8") (pinfunction "8_8") (pintype "passive"))
      (node (ref "R3.3") (pin "7") (pinfunction "2_7") (pintype "passive"))
    )
    (net (code "77") (name "Net-(R3.3C-2)") (class "Default")
      (node (ref "J3.2") (pin "10") (pinfunction "10_10") (pintype "passive"))
      (node (ref "J3.2") (pin "11") (pinfunction "11_11") (pintype "passive"))
      (node (ref "J3.2") (pin "12") (pinfunction "12_12") (pintype "passive"))
      (node (ref "J3.2") (pin "9") (pinfunction "9_9") (pintype "passive"))
      (node (ref "R3.3") (pin "6") (pinfunction "2_6") (pintype "passive"))
    )
    (net (code "78") (name "Net-(R3.3D-2)") (class "Default")
      (node (ref "J3.2") (pin "13") (pinfunction "13_13") (pintype "passive"))
      (node (ref "J3.2") (pin "14") (pinfunction "14_14") (pintype "passive"))
      (node (ref "J3.2") (pin "15") (pinfunction "15_15") (pintype "passive"))
      (node (ref "J3.2") (pin "16") (pinfunction "16_16") (pintype "passive"))
      (node (ref "R3.3") (pin "5") (pinfunction "2_5") (pintype "passive"))
    )
    (net (code "79") (name "Net-(R4.2A-2)") (class "Default")
      (node (ref "D4.1") (pin "C") (pinfunction "C_C") (pintype "passive"))
      (node (ref "R4.2") (pin "8") (pinfunction "2_8") (pintype "passive"))
    )
    (net (code "80") (name "Net-(R4.2B-2)") (class "Default")
      (node (ref "D4.2") (pin "C") (pinfunction "C_C") (pintype "passive"))
      (node (ref "R4.2") (pin "7") (pinfunction "2_7") (pintype "passive"))
    )
    (net (code "81") (name "Net-(R4.2C-2)") (class "Default")
      (node (ref "D4.3") (pin "C") (pinfunction "C_C") (pintype "passive"))
      (node (ref "R4.2") (pin "6") (pinfunction "2_6") (pintype "passive"))
    )
    (net (code "82") (name "Net-(R4.2D-2)") (class "Default")
      (node (ref "D4.4") (pin "C") (pinfunction "C_C") (pintype "passive"))
      (node (ref "R4.2") (pin "5") (pinfunction "2_5") (pintype "passive"))
    )
    (net (code "83") (name "Net-(R4.3A-2)") (class "Default")
      (node (ref "J4.2") (pin "1") (pinfunction "1_1") (pintype "passive"))
      (node (ref "J4.2") (pin "2") (pinfunction "2_2") (pintype "passive"))
      (node (ref "J4.2") (pin "3") (pinfunction "3_3") (pintype "passive"))
      (node (ref "J4.2") (pin "4") (pinfunction "4_4") (pintype "passive"))
      (node (ref "R4.3") (pin "8") (pinfunction "2_8") (pintype "passive"))
    )
    (net (code "84") (name "Net-(R4.3B-2)") (class "Default")
      (node (ref "J4.2") (pin "5") (pinfunction "5_5") (pintype "passive"))
      (node (ref "J4.2") (pin "6") (pinfunction "6_6") (pintype "passive"))
      (node (ref "J4.2") (pin "7") (pinfunction "7_7") (pintype "passive"))
      (node (ref "J4.2") (pin "8") (pinfunction "8_8") (pintype "passive"))
      (node (ref "R4.3") (pin "7") (pinfunction "2_7") (pintype "passive"))
    )
    (net (code "85") (name "Net-(R4.3C-2)") (class "Default")
      (node (ref "J4.2") (pin "10") (pinfunction "10_10") (pintype "passive"))
      (node (ref "J4.2") (pin "11") (pinfunction "11_11") (pintype "passive"))
      (node (ref "J4.2") (pin "12") (pinfunction "12_12") (pintype "passive"))
      (node (ref "J4.2") (pin "9") (pinfunction "9_9") (pintype "passive"))
      (node (ref "R4.3") (pin "6") (pinfunction "2_6") (pintype "passive"))
    )
    (net (code "86") (name "Net-(R4.3D-2)") (class "Default")
      (node (ref "J4.2") (pin "13") (pinfunction "13_13") (pintype "passive"))
      (node (ref "J4.2") (pin "14") (pinfunction "14_14") (pintype "passive"))
      (node (ref "J4.2") (pin "15") (pinfunction "15_15") (pintype "passive"))
      (node (ref "J4.2") (pin "16") (pinfunction "16_16") (pintype "passive"))
      (node (ref "R4.3") (pin "5") (pinfunction "2_5") (pintype "passive"))
    )
    (net (code "87") (name "Net-(RI.1B-1)") (class "Default")
      (node (ref "JI.1") (pin "5") (pinfunction "5_5") (pintype "passive"))
      (node (ref "JI.1") (pin "6") (pinfunction "6_6") (pintype "passive"))
      (node (ref "JI.1") (pin "7") (pinfunction "7_7") (pintype "passive"))
      (node (ref "JI.1") (pin "8") (pinfunction "8_8") (pintype "passive"))
      (node (ref "RI.1") (pin "2") (pinfunction "1_2") (pintype "passive"))
      (node (ref "RI.3") (pin "7") (pinfunction "2_7") (pintype "passive"))
    )
    (net (code "88") (name "Net-(RI.1C-1)") (class "Default")
      (node (ref "JI.1") (pin "10") (pinfunction "10_10") (pintype "passive"))
      (node (ref "JI.1") (pin "11") (pinfunction "11_11") (pintype "passive"))
      (node (ref "JI.1") (pin "12") (pinfunction "12_12") (pintype "passive"))
      (node (ref "JI.1") (pin "9") (pinfunction "9_9") (pintype "passive"))
      (node (ref "RI.1") (pin "3") (pinfunction "1_3") (pintype "passive"))
      (node (ref "RI.3") (pin "6") (pinfunction "2_6") (pintype "passive"))
    )
    (net (code "89") (name "Net-(RI.1D-1)") (class "Default")
      (node (ref "JI.1") (pin "13") (pinfunction "13_13") (pintype "passive"))
      (node (ref "JI.1") (pin "14") (pinfunction "14_14") (pintype "passive"))
      (node (ref "JI.1") (pin "15") (pinfunction "15_15") (pintype "passive"))
      (node (ref "JI.1") (pin "16") (pinfunction "16_16") (pintype "passive"))
      (node (ref "RI.1") (pin "4") (pinfunction "1_4") (pintype "passive"))
      (node (ref "RI.3") (pin "5") (pinfunction "2_5") (pintype "passive"))
    )
    (net (code "90") (name "Net-(RI.2B-1)") (class "Default")
      (node (ref "DI.2") (pin "C") (pinfunction "C_C") (pintype "passive"))
      (node (ref "RI.2") (pin "2") (pinfunction "1_2") (pintype "passive"))
    )
    (net (code "91") (name "Net-(RI.2C-1)") (class "Default")
      (node (ref "DI.3") (pin "C") (pinfunction "C_C") (pintype "passive"))
      (node (ref "RI.2") (pin "3") (pinfunction "1_3") (pintype "passive"))
    )
    (net (code "92") (name "Net-(RI.2D-1)") (class "Default")
      (node (ref "DI.4") (pin "C") (pinfunction "C_C") (pintype "passive"))
      (node (ref "RI.2") (pin "4") (pinfunction "1_4") (pintype "passive"))
    )
    (net (code "93") (name "Net-(RI.3A-2)") (class "Default")
      (node (ref "JI.1") (pin "1") (pinfunction "1_1") (pintype "passive"))
      (node (ref "JI.1") (pin "2") (pinfunction "2_2") (pintype "passive"))
      (node (ref "JI.1") (pin "3") (pinfunction "3_3") (pintype "passive"))
      (node (ref "JI.1") (pin "4") (pinfunction "4_4") (pintype "passive"))
      (node (ref "RI.1") (pin "1") (pinfunction "1_1") (pintype "passive"))
      (node (ref "RI.3") (pin "8") (pinfunction "2_8") (pintype "passive"))
    )
    (net (code "94") (name "Net-(RI.3B-1)") (class "Default")
      (node (ref "DI.2") (pin "A") (pinfunction "A_A") (pintype "passive"))
      (node (ref "RI.3") (pin "2") (pinfunction "1_2") (pintype "passive"))
      (node (ref "SI.2") (pin "3") (pinfunction "B_3") (pintype "bidirectional"))
      (node (ref "SI.2") (pin "4") (pinfunction "B_4") (pintype "bidirectional"))
    )
    (net (code "95") (name "Net-(RI.3C-1)") (class "Default")
      (node (ref "DI.3") (pin "A") (pinfunction "A_A") (pintype "passive"))
      (node (ref "RI.3") (pin "3") (pinfunction "1_3") (pintype "passive"))
      (node (ref "SI.3") (pin "3") (pinfunction "B_3") (pintype "bidirectional"))
      (node (ref "SI.3") (pin "4") (pinfunction "B_4") (pintype "bidirectional"))
    )
    (net (code "96") (name "Net-(RI.3D-1)") (class "Default")
      (node (ref "DI.4") (pin "A") (pinfunction "A_A") (pintype "passive"))
      (node (ref "RI.3") (pin "4") (pinfunction "1_4") (pintype "passive"))
      (node (ref "SI.4") (pin "3") (pinfunction "B_3") (pintype "bidirectional"))
      (node (ref "SI.4") (pin "4") (pinfunction "B_4") (pintype "bidirectional"))
    )
    (net (code "97") (name "Net-(RO.1A-2)") (class "Default")
      (node (ref "DO.1") (pin "A") (pinfunction "A_A") (pintype "passive"))
      (node (ref "JO.1") (pin "1") (pinfunction "1_1") (pintype "passive"))
      (node (ref "JO.1") (pin "2") (pinfunction "2_2") (pintype "passive"))
      (node (ref "JO.1") (pin "3") (pinfunction "3_3") (pintype "passive"))
      (node (ref "JO.1") (pin "4") (pinfunction "4_4") (pintype "passive"))
      (node (ref "RO.1") (pin "8") (pinfunction "2_8") (pintype "passive"))
    )
    (net (code "98") (name "Net-(RO.1B-2)") (class "Default")
      (node (ref "DO.2") (pin "A") (pinfunction "A_A") (pintype "passive"))
      (node (ref "JO.1") (pin "5") (pinfunction "5_5") (pintype "passive"))
      (node (ref "JO.1") (pin "6") (pinfunction "6_6") (pintype "passive"))
      (node (ref "JO.1") (pin "7") (pinfunction "7_7") (pintype "passive"))
      (node (ref "JO.1") (pin "8") (pinfunction "8_8") (pintype "passive"))
      (node (ref "RO.1") (pin "7") (pinfunction "2_7") (pintype "passive"))
    )
    (net (code "99") (name "Net-(RO.1C-2)") (class "Default")
      (node (ref "DO.3") (pin "A") (pinfunction "A_A") (pintype "passive"))
      (node (ref "JO.1") (pin "10") (pinfunction "10_10") (pintype "passive"))
      (node (ref "JO.1") (pin "11") (pinfunction "11_11") (pintype "passive"))
      (node (ref "JO.1") (pin "12") (pinfunction "12_12") (pintype "passive"))
      (node (ref "JO.1") (pin "9") (pinfunction "9_9") (pintype "passive"))
      (node (ref "RO.1") (pin "6") (pinfunction "2_6") (pintype "passive"))
    )
    (net (code "100") (name "Net-(RO.1D-2)") (class "Default")
      (node (ref "DO.4") (pin "A") (pinfunction "A_A") (pintype "passive"))
      (node (ref "JO.1") (pin "13") (pinfunction "13_13") (pintype "passive"))
      (node (ref "JO.1") (pin "14") (pinfunction "14_14") (pintype "passive"))
      (node (ref "JO.1") (pin "15") (pinfunction "15_15") (pintype "passive"))
      (node (ref "JO.1") (pin "16") (pinfunction "16_16") (pintype "passive"))
      (node (ref "RO.1") (pin "5") (pinfunction "2_5") (pintype "passive"))
    )
    (net (code "101") (name "Net-(RO.2B-1)") (class "Default")
      (node (ref "DO.2") (pin "C") (pinfunction "C_C") (pintype "passive"))
      (node (ref "RO.2") (pin "2") (pinfunction "1_2") (pintype "passive"))
    )
    (net (code "102") (name "Net-(RO.2C-1)") (class "Default")
      (node (ref "DO.3") (pin "C") (pinfunction "C_C") (pintype "passive"))
      (node (ref "RO.2") (pin "3") (pinfunction "1_3") (pintype "passive"))
    )
    (net (code "103") (name "Net-(RO.2D-1)") (class "Default")
      (node (ref "DO.4") (pin "C") (pinfunction "C_C") (pintype "passive"))
      (node (ref "RO.2") (pin "4") (pinfunction "1_4") (pintype "passive"))
    )
    (net (code "104") (name "Net-(USB-VCC)") (class "Default")
      (node (ref "CP.1") (pin "1") (pinfunction "1_1") (pintype "passive"))
      (node (ref "CP.2") (pin "1") (pinfunction "1_1") (pintype "passive"))
      (node (ref "FP.1") (pin "1") (pinfunction "1_1") (pintype "bidirectional"))
      (node (ref "JP.2") (pin "1") (pinfunction "1_1") (pintype "passive"))
      (node (ref "JP.2") (pin "2") (pinfunction "2_2") (pintype "passive"))
      (node (ref "USB") (pin "1") (pinfunction "VCC_1") (pintype "bidirectional"))
    )
    (net (code "105") (name "unconnected-(USB-D+-Pad3)") (class "Default")
      (node (ref "USB") (pin "3") (pinfunction "D+_3") (pintype "bidirectional"))
    )
    (net (code "106") (name "unconnected-(USB-D--Pad2)") (class "Default")
      (node (ref "USB") (pin "2") (pinfunction "D-_2") (pintype "bidirectional"))
    )
    (net (code "107") (name "unconnected-(USB-ID-Pad4)") (class "Default")
      (node (ref "USB") (pin "4") (pinfunction "ID_4") (pintype "bidirectional"))
    )
  )
)
